# project_buran.net
KiCad netlist of a schematic drawn in Altium Designer
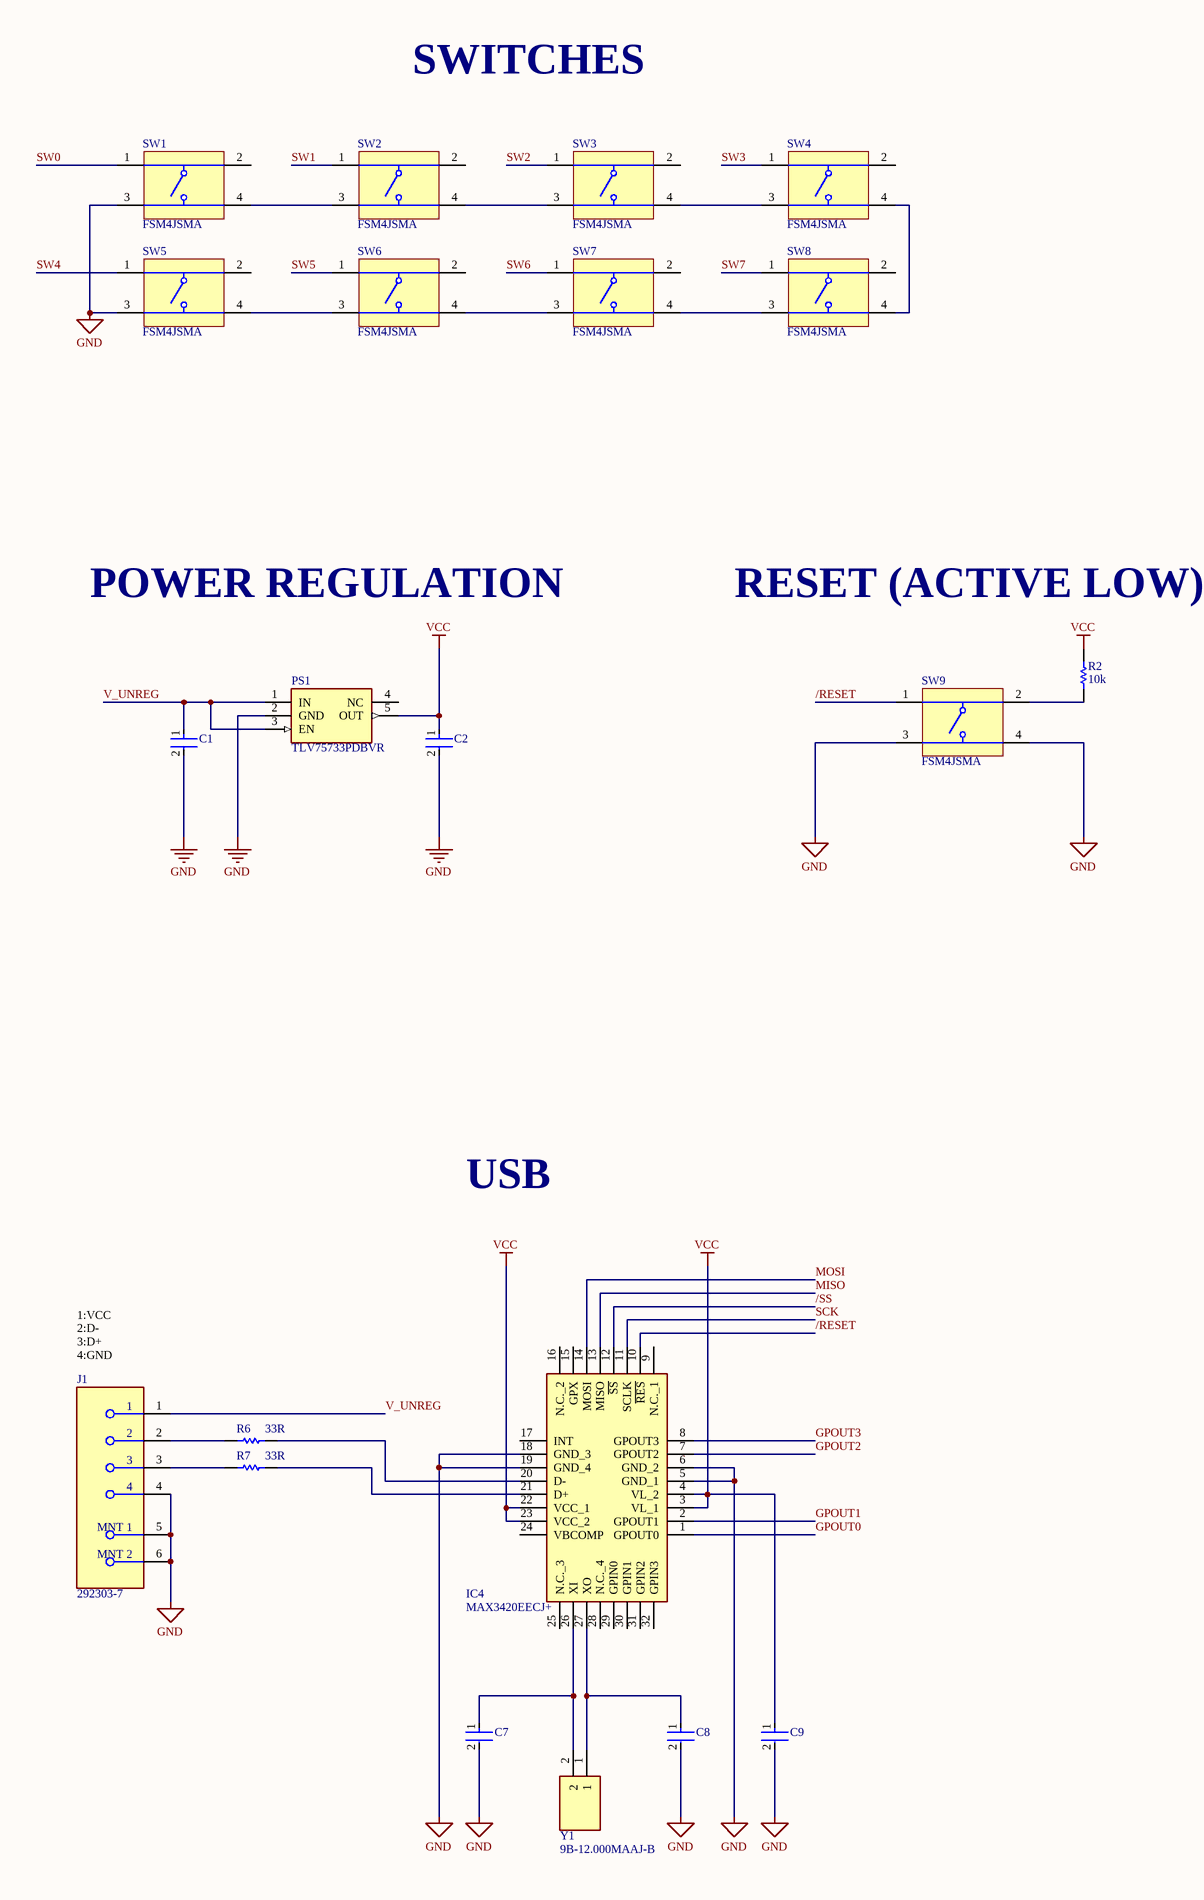
[diagram p0: project_buran.SchDoc, left]
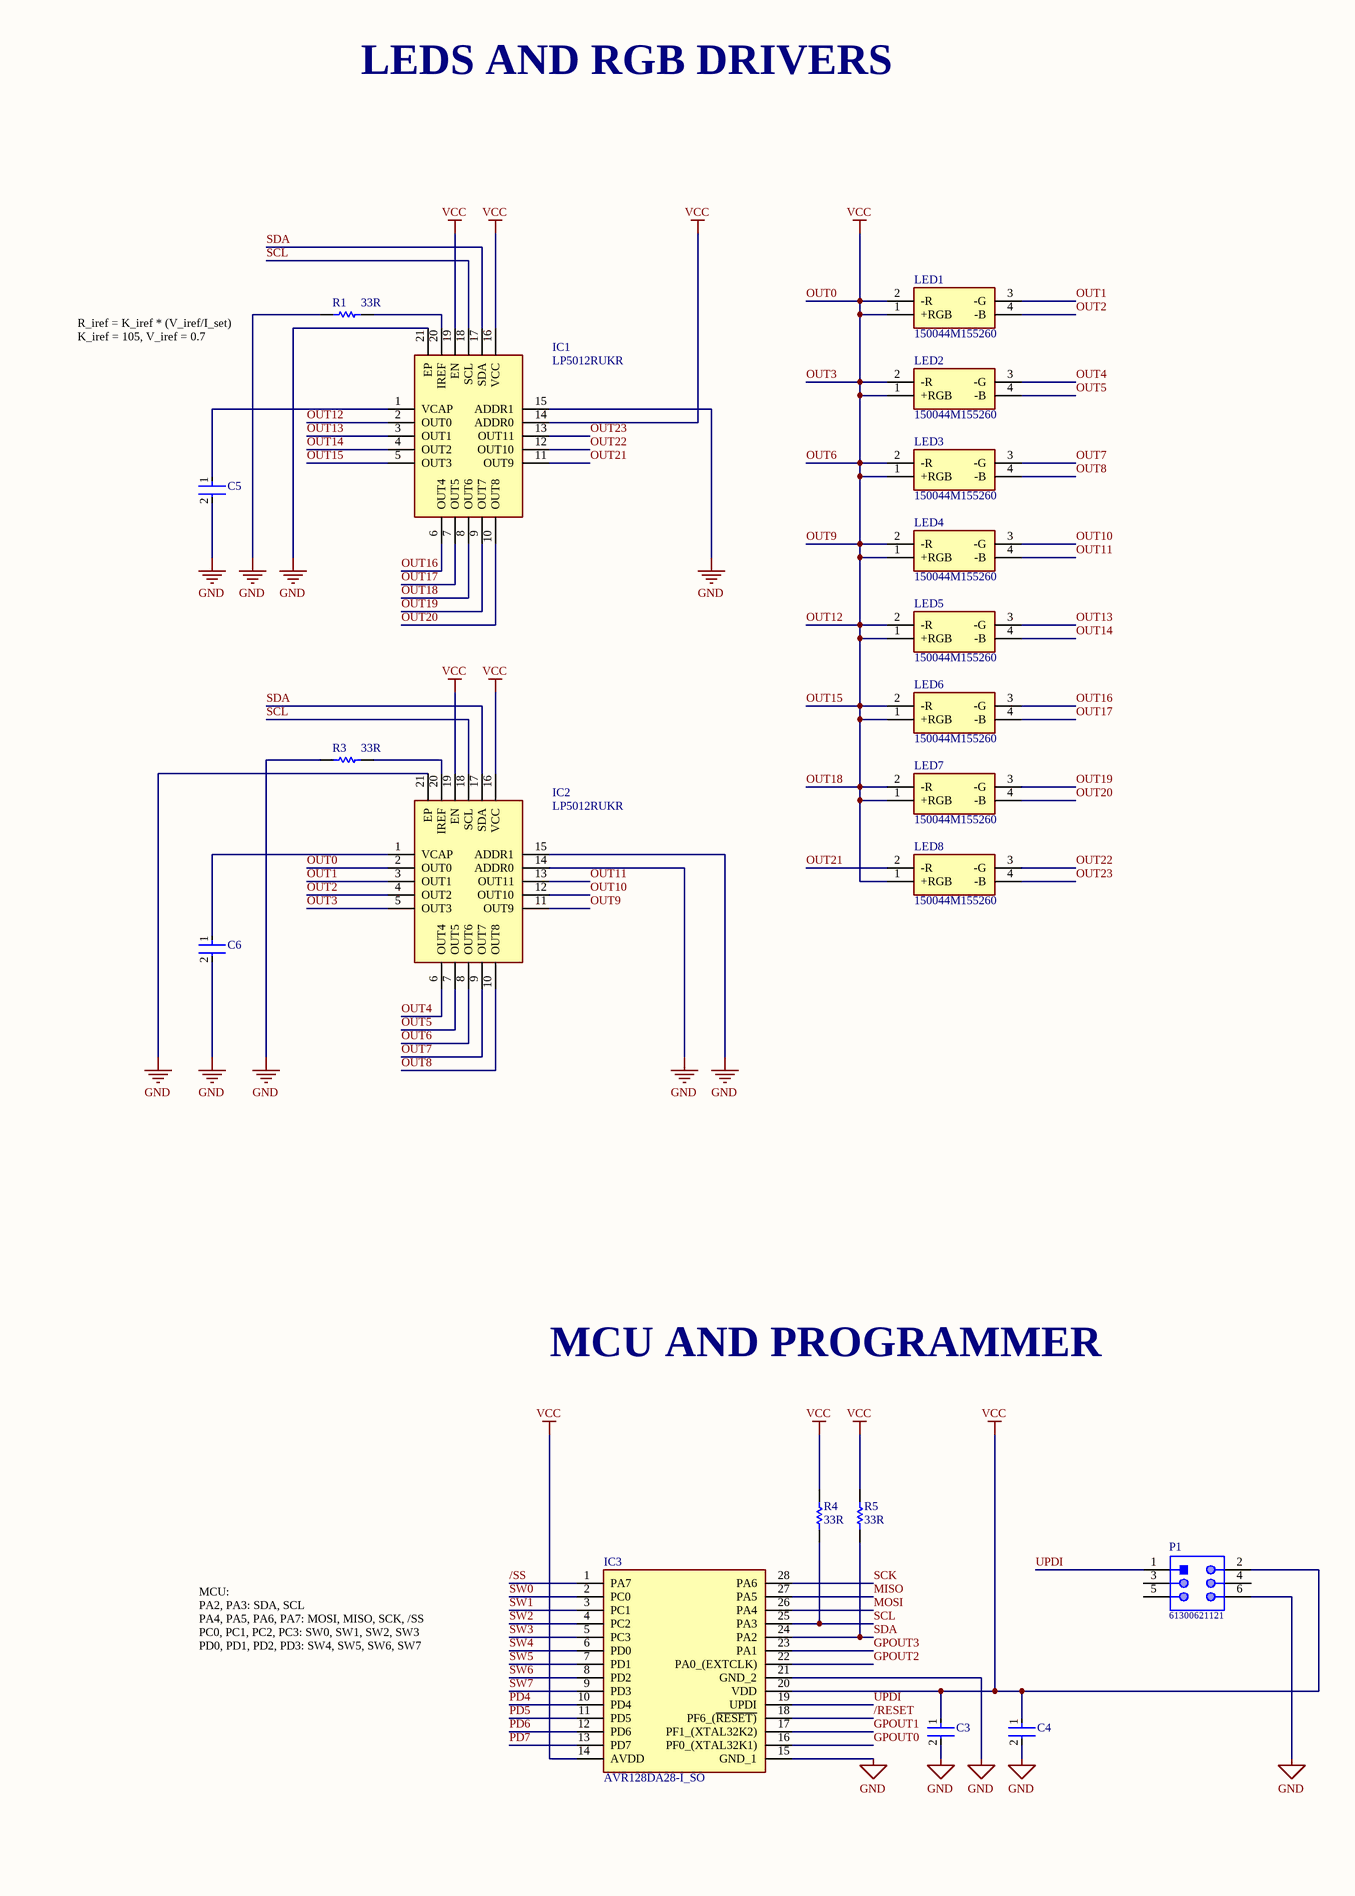
[diagram p1: project_buran.SchDoc, right]

(export (version "E")
  (design (tool "Eeschema 10.0.6"))
  (components
    (comp (ref "C1")
      (value "GRM188R60J106ME47D")
      (footprint "FP-GRM188-0_1-e0_2_0_55-IPC_A")
      (description "Chip Multilayer Ceramic Capacitors for General Purpose, 0603, 10uF, X5R, 15%, 20%, 6.3V")
      (fields (field (name "VOLTAGE") "6.3V") (field (name "TOLERANCE") "20%"))
      (libsource (lib "Altium Content Vault") (part "02cd4be3c70576c341d710602a673aa"))
    )
    (comp (ref "C2")
      (value "GRM188R60J106ME47D")
      (footprint "FP-GRM188-0_1-e0_2_0_55-IPC_A")
      (description "Chip Multilayer Ceramic Capacitors for General Purpose, 0603, 10uF, X5R, 15%, 20%, 6.3V")
      (fields (field (name "VOLTAGE") "6.3V") (field (name "TOLERANCE") "20%"))
      (libsource (lib "Altium Content Vault") (part "02cd4be3c70576c341d710602a673aa"))
    )
    (comp (ref "C3")
      (value "GRM188R60J106ME47D")
      (footprint "FP-GRM188-0_1-e0_2_0_55-IPC_A")
      (description "Chip Multilayer Ceramic Capacitors for General Purpose, 0603, 10uF, X5R, 15%, 20%, 6.3V")
      (fields (field (name "VOLTAGE") "6.3V") (field (name "TOLERANCE") "20%"))
      (libsource (lib "Altium Content Vault") (part "02cd4be3c70576c341d710602a673aa"))
    )
    (comp (ref "C4")
      (value "GRM188R60J106ME47D")
      (footprint "FP-GRM188-0_1-e0_2_0_55-IPC_A")
      (description "Chip Multilayer Ceramic Capacitors for General Purpose, 0603, 10uF, X5R, 15%, 20%, 6.3V")
      (fields (field (name "VOLTAGE") "6.3V") (field (name "TOLERANCE") "20%"))
      (libsource (lib "Altium Content Vault") (part "02cd4be3c70576c341d710602a673aa"))
    )
    (comp (ref "C5")
      (value "GRM188R60J106ME47D")
      (footprint "FP-GRM188-0_1-e0_2_0_55-IPC_A")
      (description "Chip Multilayer Ceramic Capacitors for General Purpose, 0603, 10uF, X5R, 15%, 20%, 6.3V")
      (fields (field (name "VOLTAGE") "6.3V") (field (name "TOLERANCE") "20%"))
      (libsource (lib "Altium Content Vault") (part "02cd4be3c70576c341d710602a673aa"))
    )
    (comp (ref "C6")
      (value "GRM188R60J106ME47D")
      (footprint "FP-GRM188-0_1-e0_2_0_55-IPC_A")
      (description "Chip Multilayer Ceramic Capacitors for General Purpose, 0603, 10uF, X5R, 15%, 20%, 6.3V")
      (fields (field (name "VOLTAGE") "6.3V") (field (name "TOLERANCE") "20%"))
      (libsource (lib "Altium Content Vault") (part "02cd4be3c70576c341d710602a673aa"))
    )
    (comp (ref "C7")
      (value "GRM188R60J106ME47D")
      (footprint "FP-GRM188-0_1-e0_2_0_55-IPC_A")
      (description "Chip Multilayer Ceramic Capacitors for General Purpose, 0603, 10uF, X5R, 15%, 20%, 6.3V")
      (fields (field (name "VOLTAGE") "6.3V") (field (name "TOLERANCE") "20%"))
      (libsource (lib "Altium Content Vault") (part "02cd4be3c70576c341d710602a673aa"))
    )
    (comp (ref "C8")
      (value "GRM188R60J106ME47D")
      (footprint "FP-GRM188-0_1-e0_2_0_55-IPC_A")
      (description "Chip Multilayer Ceramic Capacitors for General Purpose, 0603, 10uF, X5R, 15%, 20%, 6.3V")
      (fields (field (name "VOLTAGE") "6.3V") (field (name "TOLERANCE") "20%"))
      (libsource (lib "Altium Content Vault") (part "02cd4be3c70576c341d710602a673aa"))
    )
    (comp (ref "C9")
      (value "GRM188R60J106ME47D")
      (footprint "FP-GRM188-0_1-e0_2_0_55-IPC_A")
      (description "Chip Multilayer Ceramic Capacitors for General Purpose, 0603, 10uF, X5R, 15%, 20%, 6.3V")
      (fields (field (name "VOLTAGE") "6.3V") (field (name "TOLERANCE") "20%"))
      (libsource (lib "Altium Content Vault") (part "02cd4be3c70576c341d710602a673aa"))
    )
    (comp (ref "IC1")
      (value "LP5012RUKR")
      (footprint "SamacSys:QFN40P300X300X80-21N-D")
      (description "Integrated Circuit")
      (fields (field (name "MOUSER PART NUMBER") "595-LP5012RUKR"))
      (libsource (lib "*") (part "LP5012RUKR"))
    )
    (comp (ref "IC2")
      (value "LP5012RUKR")
      (footprint "SamacSys:QFN40P300X300X80-21N-D")
      (description "Integrated Circuit")
      (fields (field (name "MOUSER PART NUMBER") "595-LP5012RUKR"))
      (libsource (lib "*") (part "LP5012RUKR"))
    )
    (comp (ref "IC3")
      (value "AVR128DA28-I_SO")
      (footprint "SamacSys:SOIC127P1030X265-28N")
      (description "Integrated Circuit")
      (fields
        (field (name "MANUFACTURER_PART_NUMBER") "AVR128DA28-I/SO")
        (field (name "MOUSER PART NUMBER") "579-AVR128DA28-I/SO")
      )
      (libsource (lib "*") (part "AVR128DA28-I_SO"))
    )
    (comp (ref "IC4")
      (value "MAX3420EECJ+")
      (footprint "SamacSys:QFP80P900X900X160-32N")
      (description "Integrated Circuit")
      (fields (field (name "MOUSER PART NUMBER") "700-MAX3420EECJ"))
      (libsource (lib "*") (part "MAX3420EECJ+"))
    )
    (comp (ref "J1")
      (value "292303-7")
      (footprint "FP-292303-7-MFG")
      (description "CONN RCPT USB2.0 TYPEA 4P SMD RA")
      (fields
        (field (name "OCTOPART") "https://octopart.com/292303-7-te+connectivity-42840369")
        (field (name "MANUFACTURER") "TE Connectivity")
      )
      (libsource (lib "Altium Content Vault") (part "79e6714efa0bb2f851c24b2688127c9"))
    )
    (comp (ref "LED1")
      (value "150044M155260")
      (footprint "SamacSys:150044M155260")
      (description "LED")
      (fields (field (name "MOUSER PART NUMBER") "710-150044M155260"))
      (libsource (lib "*") (part "150044M155260"))
    )
    (comp (ref "LED2")
      (value "150044M155260")
      (footprint "SamacSys:150044M155260")
      (description "LED")
      (fields (field (name "MOUSER PART NUMBER") "710-150044M155260"))
      (libsource (lib "*") (part "150044M155260"))
    )
    (comp (ref "LED3")
      (value "150044M155260")
      (footprint "SamacSys:150044M155260")
      (description "LED")
      (fields (field (name "MOUSER PART NUMBER") "710-150044M155260"))
      (libsource (lib "*") (part "150044M155260"))
    )
    (comp (ref "LED4")
      (value "150044M155260")
      (footprint "SamacSys:150044M155260")
      (description "LED")
      (fields (field (name "MOUSER PART NUMBER") "710-150044M155260"))
      (libsource (lib "*") (part "150044M155260"))
    )
    (comp (ref "LED5")
      (value "150044M155260")
      (footprint "SamacSys:150044M155260")
      (description "LED")
      (fields (field (name "MOUSER PART NUMBER") "710-150044M155260"))
      (libsource (lib "*") (part "150044M155260"))
    )
    (comp (ref "LED6")
      (value "150044M155260")
      (footprint "SamacSys:150044M155260")
      (description "LED")
      (fields (field (name "MOUSER PART NUMBER") "710-150044M155260"))
      (libsource (lib "*") (part "150044M155260"))
    )
    (comp (ref "LED7")
      (value "150044M155260")
      (footprint "SamacSys:150044M155260")
      (description "LED")
      (fields (field (name "MOUSER PART NUMBER") "710-150044M155260"))
      (libsource (lib "*") (part "150044M155260"))
    )
    (comp (ref "LED8")
      (value "150044M155260")
      (footprint "SamacSys:150044M155260")
      (description "LED")
      (fields (field (name "MOUSER PART NUMBER") "710-150044M155260"))
      (libsource (lib "*") (part "150044M155260"))
    )
    (comp (ref "P1")
      (value "61300621121")
      (footprint "61300621121")
      (description "THT Vertical Pin Header WR-PHD, Pitch 2.54 mm, Dual Row, 6 pins")
      (fields (field (name "MANUFACTURER") "Wurth Elektronik") (field (name "PUBLISHER") "WurthElektronik"))
      (libsource (lib "Altium Content Vault") (part "WE-CN-2P-M-R6"))
    )
    (comp (ref "PS1")
      (value "TLV75733PDBVR")
      (footprint "SamacSys:SOT95P280X145-5N")
      (description "Power Supply")
      (fields (field (name "MOUSER PART NUMBER") "595-TLV75733PDBVR"))
      (libsource (lib "*") (part "TLV75733PDBVR"))
    )
    (comp (ref "R1")
      (value "33R")
      (footprint "RESC1609X50X30NL10T20")
      (fields (field (name "PART NUMBER") "CRCW0603110RFKEA") (field (name "MANUFACTURER") "Vishay Dale"))
      (libsource (lib "Altium Content Vault") (part "RES"))
    )
    (comp (ref "R2")
      (value "10k")
      (footprint "RESC1609X50X30NL10T20")
      (fields (field (name "PART NUMBER") "CRCW0603110RFKEA") (field (name "MANUFACTURER") "Vishay Dale"))
      (libsource (lib "Altium Content Vault") (part "RES"))
    )
    (comp (ref "R3")
      (value "33R")
      (footprint "RESC1609X50X30NL10T20")
      (fields (field (name "PART NUMBER") "CRCW0603110RFKEA") (field (name "MANUFACTURER") "Vishay Dale"))
      (libsource (lib "Altium Content Vault") (part "RES"))
    )
    (comp (ref "R4")
      (value "33R")
      (footprint "RESC1609X50X30NL10T20")
      (fields (field (name "PART NUMBER") "CRCW0603110RFKEA") (field (name "MANUFACTURER") "Vishay Dale"))
      (libsource (lib "Altium Content Vault") (part "RES"))
    )
    (comp (ref "R5")
      (value "33R")
      (footprint "RESC1609X50X30NL10T20")
      (fields (field (name "PART NUMBER") "CRCW0603110RFKEA") (field (name "MANUFACTURER") "Vishay Dale"))
      (libsource (lib "Altium Content Vault") (part "RES"))
    )
    (comp (ref "R6")
      (value "33R")
      (footprint "RESC1609X50X30NL10T20")
      (fields (field (name "PART NUMBER") "CRCW0603110RFKEA") (field (name "MANUFACTURER") "Vishay Dale"))
      (libsource (lib "Altium Content Vault") (part "RES"))
    )
    (comp (ref "R7")
      (value "33R")
      (footprint "RESC1609X50X30NL10T20")
      (fields (field (name "PART NUMBER") "CRCW0603110RFKEA") (field (name "MANUFACTURER") "Vishay Dale"))
      (libsource (lib "Altium Content Vault") (part "RES"))
    )
    (comp (ref "SW1")
      (value "FSM4JSMA")
      (footprint "TECO-FSM4JSMA_V")
      (description "Swicth, SPST, 24 V, -35 to 85 degC, 4-Pin SMD, RoHS, Tape and Reel")
      (fields (field (name "MANUFACTURER") "TE Connectivity"))
      (libsource (lib "Altium Content Vault") (part "SW-SPST-4_A"))
    )
    (comp (ref "SW2")
      (value "FSM4JSMA")
      (footprint "TECO-FSM4JSMA_V")
      (description "Swicth, SPST, 24 V, -35 to 85 degC, 4-Pin SMD, RoHS, Tape and Reel")
      (fields (field (name "MANUFACTURER") "TE Connectivity"))
      (libsource (lib "Altium Content Vault") (part "SW-SPST-4_A"))
    )
    (comp (ref "SW3")
      (value "FSM4JSMA")
      (footprint "TECO-FSM4JSMA_V")
      (description "Swicth, SPST, 24 V, -35 to 85 degC, 4-Pin SMD, RoHS, Tape and Reel")
      (fields (field (name "MANUFACTURER") "TE Connectivity"))
      (libsource (lib "Altium Content Vault") (part "SW-SPST-4_A"))
    )
    (comp (ref "SW4")
      (value "FSM4JSMA")
      (footprint "TECO-FSM4JSMA_V")
      (description "Swicth, SPST, 24 V, -35 to 85 degC, 4-Pin SMD, RoHS, Tape and Reel")
      (fields (field (name "MANUFACTURER") "TE Connectivity"))
      (libsource (lib "Altium Content Vault") (part "SW-SPST-4_A"))
    )
    (comp (ref "SW5")
      (value "FSM4JSMA")
      (footprint "TECO-FSM4JSMA_V")
      (description "Swicth, SPST, 24 V, -35 to 85 degC, 4-Pin SMD, RoHS, Tape and Reel")
      (fields (field (name "MANUFACTURER") "TE Connectivity"))
      (libsource (lib "Altium Content Vault") (part "SW-SPST-4_A"))
    )
    (comp (ref "SW6")
      (value "FSM4JSMA")
      (footprint "TECO-FSM4JSMA_V")
      (description "Swicth, SPST, 24 V, -35 to 85 degC, 4-Pin SMD, RoHS, Tape and Reel")
      (fields (field (name "MANUFACTURER") "TE Connectivity"))
      (libsource (lib "Altium Content Vault") (part "SW-SPST-4_A"))
    )
    (comp (ref "SW7")
      (value "FSM4JSMA")
      (footprint "TECO-FSM4JSMA_V")
      (description "Swicth, SPST, 24 V, -35 to 85 degC, 4-Pin SMD, RoHS, Tape and Reel")
      (fields (field (name "MANUFACTURER") "TE Connectivity"))
      (libsource (lib "Altium Content Vault") (part "SW-SPST-4_A"))
    )
    (comp (ref "SW8")
      (value "FSM4JSMA")
      (footprint "TECO-FSM4JSMA_V")
      (description "Swicth, SPST, 24 V, -35 to 85 degC, 4-Pin SMD, RoHS, Tape and Reel")
      (fields (field (name "MANUFACTURER") "TE Connectivity"))
      (libsource (lib "Altium Content Vault") (part "SW-SPST-4_A"))
    )
    (comp (ref "SW9")
      (value "FSM4JSMA")
      (footprint "TECO-FSM4JSMA_V")
      (description "Swicth, SPST, 24 V, -35 to 85 degC, 4-Pin SMD, RoHS, Tape and Reel")
      (fields (field (name "MANUFACTURER") "TE Connectivity"))
      (libsource (lib "Altium Content Vault") (part "SW-SPST-4_A"))
    )
    (comp (ref "Y1")
      (value "9B-12.000MAAJ-B")
      (footprint "SamacSys:9B12000MAAJB")
      (description "Crystal or Oscillator")
      (fields (field (name "MOUSER PART NUMBER") "717-9B-12.000MAAJ-B"))
      (libsource (lib "*") (part "9B-12.000MAAJ-B"))
    )
  )
  (nets
    (net (code "1") (name "/GPOUT0") (class "Default")
      (node (ref "IC3") (pin "16") (pinfunction "PF0_(XTAL32K1)_16") (pintype "passive"))
      (node (ref "IC4") (pin "1") (pinfunction "GPOUT0_1") (pintype "passive"))
    )
    (net (code "2") (name "/GPOUT1") (class "Default")
      (node (ref "IC3") (pin "17") (pinfunction "PF1_(XTAL32K2)_17") (pintype "passive"))
      (node (ref "IC4") (pin "2") (pinfunction "GPOUT1_2") (pintype "passive"))
    )
    (net (code "3") (name "/GPOUT2") (class "Default")
      (node (ref "IC3") (pin "22") (pinfunction "PA0_(EXTCLK)_22") (pintype "passive"))
      (node (ref "IC4") (pin "7") (pinfunction "GPOUT2_7") (pintype "passive"))
    )
    (net (code "4") (name "/GPOUT3") (class "Default")
      (node (ref "IC3") (pin "23") (pinfunction "PA1_23") (pintype "passive"))
      (node (ref "IC4") (pin "8") (pinfunction "GPOUT3_8") (pintype "passive"))
    )
    (net (code "5") (name "/MISO") (class "Default")
      (node (ref "IC3") (pin "27") (pinfunction "PA5_27") (pintype "passive"))
      (node (ref "IC4") (pin "13") (pinfunction "MISO_13") (pintype "passive"))
    )
    (net (code "6") (name "/MOSI") (class "Default")
      (node (ref "IC3") (pin "26") (pinfunction "PA4_26") (pintype "passive"))
      (node (ref "IC4") (pin "14") (pinfunction "MOSI_14") (pintype "passive"))
    )
    (net (code "7") (name "/OUT1") (class "Default")
      (node (ref "IC2") (pin "3") (pinfunction "OUT1_3") (pintype "passive"))
      (node (ref "LED1") (pin "3") (pinfunction "-G_3") (pintype "passive"))
    )
    (net (code "8") (name "/OUT2") (class "Default")
      (node (ref "IC2") (pin "4") (pinfunction "OUT2_4") (pintype "passive"))
      (node (ref "LED1") (pin "4") (pinfunction "-B_4") (pintype "passive"))
    )
    (net (code "9") (name "/OUT4") (class "Default")
      (node (ref "IC2") (pin "6") (pinfunction "OUT4_6") (pintype "passive"))
      (node (ref "LED2") (pin "3") (pinfunction "-G_3") (pintype "passive"))
    )
    (net (code "10") (name "/OUT5") (class "Default")
      (node (ref "IC2") (pin "7") (pinfunction "OUT5_7") (pintype "passive"))
      (node (ref "LED2") (pin "4") (pinfunction "-B_4") (pintype "passive"))
    )
    (net (code "11") (name "/OUT7") (class "Default")
      (node (ref "IC2") (pin "9") (pinfunction "OUT7_9") (pintype "passive"))
      (node (ref "LED3") (pin "3") (pinfunction "-G_3") (pintype "passive"))
    )
    (net (code "12") (name "/OUT8") (class "Default")
      (node (ref "IC2") (pin "10") (pinfunction "OUT8_10") (pintype "passive"))
      (node (ref "LED3") (pin "4") (pinfunction "-B_4") (pintype "passive"))
    )
    (net (code "13") (name "/OUT10") (class "Default")
      (node (ref "IC2") (pin "12") (pinfunction "OUT10_12") (pintype "passive"))
      (node (ref "LED4") (pin "3") (pinfunction "-G_3") (pintype "passive"))
    )
    (net (code "14") (name "/OUT11") (class "Default")
      (node (ref "IC2") (pin "13") (pinfunction "OUT11_13") (pintype "passive"))
      (node (ref "LED4") (pin "4") (pinfunction "-B_4") (pintype "passive"))
    )
    (net (code "15") (name "/OUT13") (class "Default")
      (node (ref "IC1") (pin "3") (pinfunction "OUT1_3") (pintype "passive"))
      (node (ref "LED5") (pin "3") (pinfunction "-G_3") (pintype "passive"))
    )
    (net (code "16") (name "/OUT14") (class "Default")
      (node (ref "IC1") (pin "4") (pinfunction "OUT2_4") (pintype "passive"))
      (node (ref "LED5") (pin "4") (pinfunction "-B_4") (pintype "passive"))
    )
    (net (code "17") (name "/OUT16") (class "Default")
      (node (ref "IC1") (pin "6") (pinfunction "OUT4_6") (pintype "passive"))
      (node (ref "LED6") (pin "3") (pinfunction "-G_3") (pintype "passive"))
    )
    (net (code "18") (name "/OUT17") (class "Default")
      (node (ref "IC1") (pin "7") (pinfunction "OUT5_7") (pintype "passive"))
      (node (ref "LED6") (pin "4") (pinfunction "-B_4") (pintype "passive"))
    )
    (net (code "19") (name "/OUT19") (class "Default")
      (node (ref "IC1") (pin "9") (pinfunction "OUT7_9") (pintype "passive"))
      (node (ref "LED7") (pin "3") (pinfunction "-G_3") (pintype "passive"))
    )
    (net (code "20") (name "/OUT20") (class "Default")
      (node (ref "IC1") (pin "10") (pinfunction "OUT8_10") (pintype "passive"))
      (node (ref "LED7") (pin "4") (pinfunction "-B_4") (pintype "passive"))
    )
    (net (code "21") (name "/OUT21") (class "Default")
      (node (ref "IC1") (pin "11") (pinfunction "OUT9_11") (pintype "passive"))
      (node (ref "LED8") (pin "2") (pinfunction "-R_2") (pintype "passive"))
    )
    (net (code "22") (name "/OUT22") (class "Default")
      (node (ref "IC1") (pin "12") (pinfunction "OUT10_12") (pintype "passive"))
      (node (ref "LED8") (pin "3") (pinfunction "-G_3") (pintype "passive"))
    )
    (net (code "23") (name "/OUT23") (class "Default")
      (node (ref "IC1") (pin "13") (pinfunction "OUT11_13") (pintype "passive"))
      (node (ref "LED8") (pin "4") (pinfunction "-B_4") (pintype "passive"))
    )
    (net (code "24") (name "/PD4") (class "Default")
      (node (ref "IC3") (pin "10") (pinfunction "PD4_10") (pintype "passive"))
    )
    (net (code "25") (name "/PD5") (class "Default")
      (node (ref "IC3") (pin "11") (pinfunction "PD5_11") (pintype "passive"))
    )
    (net (code "26") (name "/PD6") (class "Default")
      (node (ref "IC3") (pin "12") (pinfunction "PD6_12") (pintype "passive"))
    )
    (net (code "27") (name "/PD7") (class "Default")
      (node (ref "IC3") (pin "13") (pinfunction "PD7_13") (pintype "passive"))
    )
    (net (code "28") (name "/SCK") (class "Default")
      (node (ref "IC3") (pin "28") (pinfunction "PA6_28") (pintype "passive"))
      (node (ref "IC4") (pin "11") (pinfunction "SCLK_11") (pintype "passive"))
    )
    (net (code "29") (name "/SCL") (class "Default")
      (node (ref "IC1") (pin "18") (pinfunction "SCL_18") (pintype "passive"))
      (node (ref "IC2") (pin "18") (pinfunction "SCL_18") (pintype "passive"))
      (node (ref "IC3") (pin "25") (pinfunction "PA3_25") (pintype "passive"))
      (node (ref "R4") (pin "1") (pinfunction "1_1") (pintype "passive"))
    )
    (net (code "30") (name "/SDA") (class "Default")
      (node (ref "IC1") (pin "17") (pinfunction "SDA_17") (pintype "passive"))
      (node (ref "IC2") (pin "17") (pinfunction "SDA_17") (pintype "passive"))
      (node (ref "IC3") (pin "24") (pinfunction "PA2_24") (pintype "passive"))
      (node (ref "R5") (pin "1") (pinfunction "1_1") (pintype "passive"))
    )
    (net (code "31") (name "/SW0") (class "Default")
      (node (ref "IC3") (pin "2") (pinfunction "PC0_2") (pintype "passive"))
      (node (ref "SW1") (pin "1") (pinfunction "1_1") (pintype "passive"))
    )
    (net (code "32") (name "/SW1") (class "Default")
      (node (ref "IC3") (pin "3") (pinfunction "PC1_3") (pintype "passive"))
      (node (ref "SW2") (pin "1") (pinfunction "1_1") (pintype "passive"))
    )
    (net (code "33") (name "/SW2") (class "Default")
      (node (ref "IC3") (pin "4") (pinfunction "PC2_4") (pintype "passive"))
      (node (ref "SW3") (pin "1") (pinfunction "1_1") (pintype "passive"))
    )
    (net (code "34") (name "/SW3") (class "Default")
      (node (ref "IC3") (pin "5") (pinfunction "PC3_5") (pintype "passive"))
      (node (ref "SW4") (pin "1") (pinfunction "1_1") (pintype "passive"))
    )
    (net (code "35") (name "/SW4") (class "Default")
      (node (ref "IC3") (pin "6") (pinfunction "PD0_6") (pintype "passive"))
      (node (ref "SW5") (pin "1") (pinfunction "1_1") (pintype "passive"))
    )
    (net (code "36") (name "/SW5") (class "Default")
      (node (ref "IC3") (pin "7") (pinfunction "PD1_7") (pintype "passive"))
      (node (ref "SW6") (pin "1") (pinfunction "1_1") (pintype "passive"))
    )
    (net (code "37") (name "/SW6") (class "Default")
      (node (ref "IC3") (pin "8") (pinfunction "PD2_8") (pintype "passive"))
      (node (ref "SW7") (pin "1") (pinfunction "1_1") (pintype "passive"))
    )
    (net (code "38") (name "/SW7") (class "Default")
      (node (ref "IC3") (pin "9") (pinfunction "PD3_9") (pintype "passive"))
      (node (ref "SW8") (pin "1") (pinfunction "1_1") (pintype "passive"))
    )
    (net (code "39") (name "/UPDI") (class "Default")
      (node (ref "IC3") (pin "19") (pinfunction "UPDI_19") (pintype "passive"))
      (node (ref "P1") (pin "1") (pinfunction "1_1") (pintype "passive"))
    )
    (net (code "40") (name "/V_UNREG") (class "Default")
      (node (ref "C1") (pin "1") (pinfunction "1_1") (pintype "passive"))
      (node (ref "J1") (pin "1") (pinfunction "1_1") (pintype "passive"))
      (node (ref "PS1") (pin "1") (pinfunction "IN_1") (pintype "power_in"))
      (node (ref "PS1") (pin "3") (pinfunction "EN_3") (pintype "input"))
    )
    (net (code "41") (name "/{slash}RESET") (class "Default")
      (node (ref "IC3") (pin "18") (pinfunction "PF6_(~{RESET)}_18") (pintype "passive"))
      (node (ref "IC4") (pin "10") (pinfunction "~{RES}_10") (pintype "passive"))
      (node (ref "SW9") (pin "1") (pinfunction "1_1") (pintype "passive"))
    )
    (net (code "42") (name "/{slash}SS") (class "Default")
      (node (ref "IC3") (pin "1") (pinfunction "PA7_1") (pintype "passive"))
      (node (ref "IC4") (pin "12") (pinfunction "~{SS}_12") (pintype "passive"))
    )
    (net (code "43") (name "GND") (class "Default")
      (node (ref "C1") (pin "2") (pinfunction "2_2") (pintype "passive"))
      (node (ref "C2") (pin "2") (pinfunction "2_2") (pintype "passive"))
      (node (ref "C3") (pin "2") (pinfunction "2_2") (pintype "passive"))
      (node (ref "C4") (pin "2") (pinfunction "2_2") (pintype "passive"))
      (node (ref "C5") (pin "2") (pinfunction "2_2") (pintype "passive"))
      (node (ref "C6") (pin "2") (pinfunction "2_2") (pintype "passive"))
      (node (ref "C7") (pin "2") (pinfunction "2_2") (pintype "passive"))
      (node (ref "C8") (pin "2") (pinfunction "2_2") (pintype "passive"))
      (node (ref "C9") (pin "2") (pinfunction "2_2") (pintype "passive"))
      (node (ref "IC1") (pin "15") (pinfunction "ADDR1_15") (pintype "passive"))
      (node (ref "IC1") (pin "21") (pinfunction "EP_21") (pintype "passive"))
      (node (ref "IC2") (pin "14") (pinfunction "ADDR0_14") (pintype "passive"))
      (node (ref "IC2") (pin "15") (pinfunction "ADDR1_15") (pintype "passive"))
      (node (ref "IC2") (pin "21") (pinfunction "EP_21") (pintype "passive"))
      (node (ref "IC3") (pin "15") (pinfunction "GND_1_15") (pintype "passive"))
      (node (ref "IC3") (pin "21") (pinfunction "GND_2_21") (pintype "passive"))
      (node (ref "IC4") (pin "18") (pinfunction "GND_3_18") (pintype "passive"))
      (node (ref "IC4") (pin "19") (pinfunction "GND_4_19") (pintype "passive"))
      (node (ref "IC4") (pin "5") (pinfunction "GND_1_5") (pintype "passive"))
      (node (ref "IC4") (pin "6") (pinfunction "GND_2_6") (pintype "passive"))
      (node (ref "J1") (pin "4") (pinfunction "4_4") (pintype "passive"))
      (node (ref "J1") (pin "5") (pinfunction "MNT_1_5") (pintype "passive"))
      (node (ref "J1") (pin "6") (pinfunction "MNT_2_6") (pintype "passive"))
      (node (ref "P1") (pin "6") (pinfunction "6_6") (pintype "passive"))
      (node (ref "PS1") (pin "2") (pinfunction "GND_2") (pintype "power_in"))
      (node (ref "R1") (pin "1") (pinfunction "1_1") (pintype "passive"))
      (node (ref "R3") (pin "1") (pinfunction "1_1") (pintype "passive"))
      (node (ref "SW1") (pin "3") (pinfunction "3_3") (pintype "passive"))
      (node (ref "SW5") (pin "3") (pinfunction "3_3") (pintype "passive"))
      (node (ref "SW9") (pin "3") (pinfunction "3_3") (pintype "passive"))
      (node (ref "SW9") (pin "4") (pinfunction "4_4") (pintype "passive"))
    )
    (net (code "44") (name "Net-(IC1-IREF)") (class "Default")
      (node (ref "IC1") (pin "20") (pinfunction "IREF_20") (pintype "passive"))
      (node (ref "R1") (pin "2") (pinfunction "2_2") (pintype "passive"))
    )
    (net (code "45") (name "Net-(IC1-VCAP)") (class "Default")
      (node (ref "C5") (pin "1") (pinfunction "1_1") (pintype "passive"))
      (node (ref "IC1") (pin "1") (pinfunction "VCAP_1") (pintype "passive"))
    )
    (net (code "46") (name "Net-(IC2-IREF)") (class "Default")
      (node (ref "IC2") (pin "20") (pinfunction "IREF_20") (pintype "passive"))
      (node (ref "R3") (pin "2") (pinfunction "2_2") (pintype "passive"))
    )
    (net (code "47") (name "Net-(IC2-VCAP)") (class "Default")
      (node (ref "C6") (pin "1") (pinfunction "1_1") (pintype "passive"))
      (node (ref "IC2") (pin "1") (pinfunction "VCAP_1") (pintype "passive"))
    )
    (net (code "48") (name "Net-(IC4-D+)") (class "Default")
      (node (ref "IC4") (pin "21") (pinfunction "D+_21") (pintype "passive"))
      (node (ref "R7") (pin "2") (pinfunction "2_2") (pintype "passive"))
    )
    (net (code "49") (name "Net-(IC4-D-)") (class "Default")
      (node (ref "IC4") (pin "20") (pinfunction "D-_20") (pintype "passive"))
      (node (ref "R6") (pin "2") (pinfunction "2_2") (pintype "passive"))
    )
    (net (code "50") (name "Net-(IC4-XI)") (class "Default")
      (node (ref "C7") (pin "1") (pinfunction "1_1") (pintype "passive"))
      (node (ref "IC4") (pin "26") (pinfunction "XI_26") (pintype "passive"))
      (node (ref "Y1") (pin "2") (pinfunction "2_2") (pintype "passive"))
    )
    (net (code "51") (name "Net-(IC4-XO)") (class "Default")
      (node (ref "C8") (pin "1") (pinfunction "1_1") (pintype "passive"))
      (node (ref "IC4") (pin "27") (pinfunction "XO_27") (pintype "passive"))
      (node (ref "Y1") (pin "1") (pinfunction "1_1") (pintype "passive"))
    )
    (net (code "52") (name "Net-(J1-Pad2)") (class "Default")
      (node (ref "J1") (pin "2") (pinfunction "2_2") (pintype "passive"))
      (node (ref "R6") (pin "1") (pinfunction "1_1") (pintype "passive"))
    )
    (net (code "53") (name "Net-(J1-Pad3)") (class "Default")
      (node (ref "J1") (pin "3") (pinfunction "3_3") (pintype "passive"))
      (node (ref "R7") (pin "1") (pinfunction "1_1") (pintype "passive"))
    )
    (net (code "54") (name "Net-(R2-Pad1)") (class "Default")
      (node (ref "R2") (pin "1") (pinfunction "1_1") (pintype "passive"))
      (node (ref "SW9") (pin "2") (pinfunction "2_2") (pintype "passive"))
    )
    (net (code "55") (name "Net-(SW1-Pad4)") (class "Default")
      (node (ref "SW1") (pin "4") (pinfunction "4_4") (pintype "passive"))
      (node (ref "SW2") (pin "3") (pinfunction "3_3") (pintype "passive"))
    )
    (net (code "56") (name "Net-(SW2-Pad4)") (class "Default")
      (node (ref "SW2") (pin "4") (pinfunction "4_4") (pintype "passive"))
      (node (ref "SW3") (pin "3") (pinfunction "3_3") (pintype "passive"))
    )
    (net (code "57") (name "Net-(SW3-Pad4)") (class "Default")
      (node (ref "SW3") (pin "4") (pinfunction "4_4") (pintype "passive"))
      (node (ref "SW4") (pin "3") (pinfunction "3_3") (pintype "passive"))
    )
    (net (code "58") (name "Net-(SW4-Pad4)") (class "Default")
      (node (ref "SW4") (pin "4") (pinfunction "4_4") (pintype "passive"))
      (node (ref "SW8") (pin "4") (pinfunction "4_4") (pintype "passive"))
    )
    (net (code "59") (name "Net-(SW5-Pad4)") (class "Default")
      (node (ref "SW5") (pin "4") (pinfunction "4_4") (pintype "passive"))
      (node (ref "SW6") (pin "3") (pinfunction "3_3") (pintype "passive"))
    )
    (net (code "60") (name "Net-(SW6-Pad4)") (class "Default")
      (node (ref "SW6") (pin "4") (pinfunction "4_4") (pintype "passive"))
      (node (ref "SW7") (pin "3") (pinfunction "3_3") (pintype "passive"))
    )
    (net (code "61") (name "Net-(SW7-Pad4)") (class "Default")
      (node (ref "SW7") (pin "4") (pinfunction "4_4") (pintype "passive"))
      (node (ref "SW8") (pin "3") (pinfunction "3_3") (pintype "passive"))
    )
    (net (code "62") (name "VCC") (class "Default")
      (node (ref "C2") (pin "1") (pinfunction "1_1") (pintype "passive"))
      (node (ref "C3") (pin "1") (pinfunction "1_1") (pintype "passive"))
      (node (ref "C4") (pin "1") (pinfunction "1_1") (pintype "passive"))
      (node (ref "C9") (pin "1") (pinfunction "1_1") (pintype "passive"))
      (node (ref "IC1") (pin "14") (pinfunction "ADDR0_14") (pintype "passive"))
      (node (ref "IC1") (pin "16") (pinfunction "VCC_16") (pintype "passive"))
      (node (ref "IC1") (pin "19") (pinfunction "EN_19") (pintype "passive"))
      (node (ref "IC1") (pin "2") (pinfunction "OUT0_2") (pintype "passive"))
      (node (ref "IC1") (pin "5") (pinfunction "OUT3_5") (pintype "passive"))
      (node (ref "IC1") (pin "8") (pinfunction "OUT6_8") (pintype "passive"))
      (node (ref "IC2") (pin "11") (pinfunction "OUT9_11") (pintype "passive"))
      (node (ref "IC2") (pin "16") (pinfunction "VCC_16") (pintype "passive"))
      (node (ref "IC2") (pin "19") (pinfunction "EN_19") (pintype "passive"))
      (node (ref "IC2") (pin "2") (pinfunction "OUT0_2") (pintype "passive"))
      (node (ref "IC2") (pin "5") (pinfunction "OUT3_5") (pintype "passive"))
      (node (ref "IC2") (pin "8") (pinfunction "OUT6_8") (pintype "passive"))
      (node (ref "IC3") (pin "14") (pinfunction "AVDD_14") (pintype "passive"))
      (node (ref "IC3") (pin "20") (pinfunction "VDD_20") (pintype "passive"))
      (node (ref "IC4") (pin "22") (pinfunction "VCC_1_22") (pintype "passive"))
      (node (ref "IC4") (pin "23") (pinfunction "VCC_2_23") (pintype "passive"))
      (node (ref "IC4") (pin "3") (pinfunction "VL_1_3") (pintype "passive"))
      (node (ref "IC4") (pin "4") (pinfunction "VL_2_4") (pintype "passive"))
      (node (ref "LED1") (pin "1") (pinfunction "+RGB_1") (pintype "passive"))
      (node (ref "LED1") (pin "2") (pinfunction "-R_2") (pintype "passive"))
      (node (ref "LED2") (pin "1") (pinfunction "+RGB_1") (pintype "passive"))
      (node (ref "LED2") (pin "2") (pinfunction "-R_2") (pintype "passive"))
      (node (ref "LED3") (pin "1") (pinfunction "+RGB_1") (pintype "passive"))
      (node (ref "LED3") (pin "2") (pinfunction "-R_2") (pintype "passive"))
      (node (ref "LED4") (pin "1") (pinfunction "+RGB_1") (pintype "passive"))
      (node (ref "LED4") (pin "2") (pinfunction "-R_2") (pintype "passive"))
      (node (ref "LED5") (pin "1") (pinfunction "+RGB_1") (pintype "passive"))
      (node (ref "LED5") (pin "2") (pinfunction "-R_2") (pintype "passive"))
      (node (ref "LED6") (pin "1") (pinfunction "+RGB_1") (pintype "passive"))
      (node (ref "LED6") (pin "2") (pinfunction "-R_2") (pintype "passive"))
      (node (ref "LED7") (pin "1") (pinfunction "+RGB_1") (pintype "passive"))
      (node (ref "LED7") (pin "2") (pinfunction "-R_2") (pintype "passive"))
      (node (ref "LED8") (pin "1") (pinfunction "+RGB_1") (pintype "passive"))
      (node (ref "P1") (pin "2") (pinfunction "2_2") (pintype "passive"))
      (node (ref "PS1") (pin "5") (pinfunction "OUT_5") (pintype "output"))
      (node (ref "R2") (pin "2") (pinfunction "2_2") (pintype "passive"))
      (node (ref "R4") (pin "2") (pinfunction "2_2") (pintype "passive"))
      (node (ref "R5") (pin "2") (pinfunction "2_2") (pintype "passive"))
    )
    (net (code "63") (name "unconnected-(IC4-GPIN0-Pad29)") (class "Default")
      (node (ref "IC4") (pin "29") (pinfunction "GPIN0_29") (pintype "passive"))
    )
    (net (code "64") (name "unconnected-(IC4-GPIN1-Pad30)") (class "Default")
      (node (ref "IC4") (pin "30") (pinfunction "GPIN1_30") (pintype "passive"))
    )
    (net (code "65") (name "unconnected-(IC4-GPIN2-Pad31)") (class "Default")
      (node (ref "IC4") (pin "31") (pinfunction "GPIN2_31") (pintype "passive"))
    )
    (net (code "66") (name "unconnected-(IC4-GPIN3-Pad32)") (class "Default")
      (node (ref "IC4") (pin "32") (pinfunction "GPIN3_32") (pintype "passive"))
    )
    (net (code "67") (name "unconnected-(IC4-GPX-Pad15)") (class "Default")
      (node (ref "IC4") (pin "15") (pinfunction "GPX_15") (pintype "passive"))
    )
    (net (code "68") (name "unconnected-(IC4-INT-Pad17)") (class "Default")
      (node (ref "IC4") (pin "17") (pinfunction "INT_17") (pintype "passive"))
    )
    (net (code "69") (name "unconnected-(IC4-N.C._1-Pad9)") (class "Default")
      (node (ref "IC4") (pin "9") (pinfunction "N.C._1_9") (pintype "passive"))
    )
    (net (code "70") (name "unconnected-(IC4-N.C._2-Pad16)") (class "Default")
      (node (ref "IC4") (pin "16") (pinfunction "N.C._2_16") (pintype "passive"))
    )
    (net (code "71") (name "unconnected-(IC4-N.C._3-Pad25)") (class "Default")
      (node (ref "IC4") (pin "25") (pinfunction "N.C._3_25") (pintype "passive"))
    )
    (net (code "72") (name "unconnected-(IC4-N.C._4-Pad28)") (class "Default")
      (node (ref "IC4") (pin "28") (pinfunction "N.C._4_28") (pintype "passive"))
    )
    (net (code "73") (name "unconnected-(IC4-VBCOMP-Pad24)") (class "Default")
      (node (ref "IC4") (pin "24") (pinfunction "VBCOMP_24") (pintype "passive"))
    )
    (net (code "74") (name "unconnected-(P1-Pad3)") (class "Default")
      (node (ref "P1") (pin "3") (pinfunction "3_3") (pintype "passive"))
    )
    (net (code "75") (name "unconnected-(P1-Pad4)") (class "Default")
      (node (ref "P1") (pin "4") (pinfunction "4_4") (pintype "passive"))
    )
    (net (code "76") (name "unconnected-(P1-Pad5)") (class "Default")
      (node (ref "P1") (pin "5") (pinfunction "5_5") (pintype "passive"))
    )
    (net (code "77") (name "unconnected-(PS1-NC-Pad4)") (class "Default")
      (node (ref "PS1") (pin "4") (pinfunction "NC_4") (pintype "passive"))
    )
    (net (code "78") (name "unconnected-(SW1-Pad2)") (class "Default")
      (node (ref "SW1") (pin "2") (pinfunction "2_2") (pintype "passive"))
    )
    (net (code "79") (name "unconnected-(SW2-Pad2)") (class "Default")
      (node (ref "SW2") (pin "2") (pinfunction "2_2") (pintype "passive"))
    )
    (net (code "80") (name "unconnected-(SW3-Pad2)") (class "Default")
      (node (ref "SW3") (pin "2") (pinfunction "2_2") (pintype "passive"))
    )
    (net (code "81") (name "unconnected-(SW4-Pad2)") (class "Default")
      (node (ref "SW4") (pin "2") (pinfunction "2_2") (pintype "passive"))
    )
    (net (code "82") (name "unconnected-(SW5-Pad2)") (class "Default")
      (node (ref "SW5") (pin "2") (pinfunction "2_2") (pintype "passive"))
    )
    (net (code "83") (name "unconnected-(SW6-Pad2)") (class "Default")
      (node (ref "SW6") (pin "2") (pinfunction "2_2") (pintype "passive"))
    )
    (net (code "84") (name "unconnected-(SW7-Pad2)") (class "Default")
      (node (ref "SW7") (pin "2") (pinfunction "2_2") (pintype "passive"))
    )
    (net (code "85") (name "unconnected-(SW8-Pad2)") (class "Default")
      (node (ref "SW8") (pin "2") (pinfunction "2_2") (pintype "passive"))
    )
  )
)
